# v1.net
KiCad netlist of a schematic drawn in EAGLE
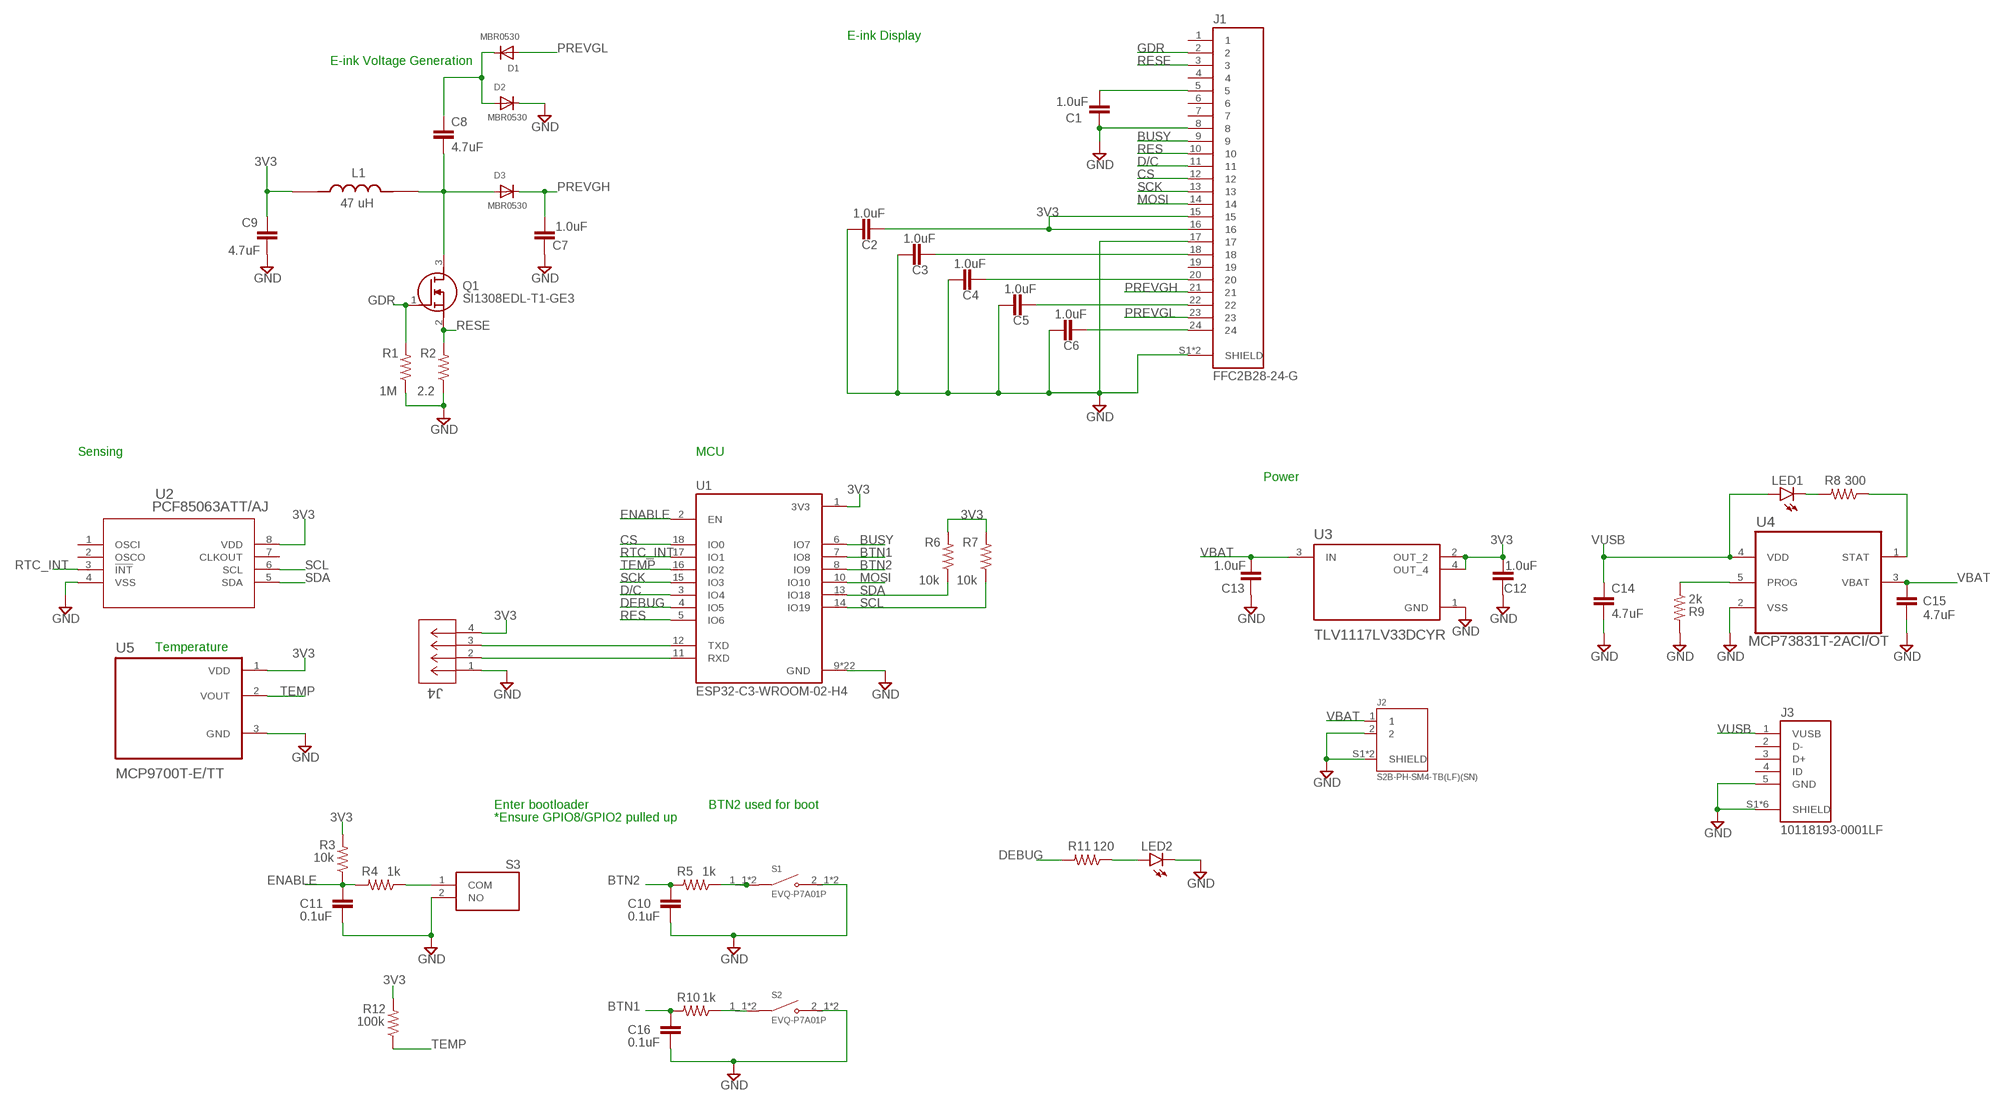
[diagram p0: schematic, sheet 1]

(export (version "E")
  (design (tool "Eeschema 10.0.6"))
  (components
    (comp (ref "C1")
      (value "1.0uF")
      (footprint "eagle-import:0603")
      (libsource (lib "eagle-import") (part "1.0UF-0603-16V-10%-X7R-WE"))
    )
    (comp (ref "C2")
      (value "1.0uF")
      (footprint "eagle-import:0603")
      (libsource (lib "eagle-import") (part "1.0UF-0603-16V-10%-X7R-WE"))
    )
    (comp (ref "C3")
      (value "1.0uF")
      (footprint "eagle-import:0603")
      (libsource (lib "eagle-import") (part "1.0UF-0603-16V-10%-X7R-WE"))
    )
    (comp (ref "C4")
      (value "1.0uF")
      (footprint "eagle-import:0603")
      (libsource (lib "eagle-import") (part "1.0UF-0603-16V-10%-X7R-WE"))
    )
    (comp (ref "C5")
      (value "1.0uF")
      (footprint "eagle-import:0603")
      (libsource (lib "eagle-import") (part "1.0UF-0603-16V-10%-X7R-WE"))
    )
    (comp (ref "C6")
      (value "1.0uF")
      (footprint "eagle-import:0603")
      (libsource (lib "eagle-import") (part "1.0UF-0603-16V-10%-X7R-WE"))
    )
    (comp (ref "C7")
      (value "1.0uF")
      (footprint "eagle-import:0603")
      (libsource (lib "eagle-import") (part "1.0UF-0603-16V-10%-X7R-WE"))
    )
    (comp (ref "C8")
      (value "4.7uF")
      (footprint "eagle-import:0603")
      (libsource (lib "eagle-import") (part "4.7UF-0603-35V-(20%)"))
    )
    (comp (ref "C9")
      (value "4.7uF")
      (footprint "eagle-import:0603")
      (libsource (lib "eagle-import") (part "4.7UF-0603-35V-(20%)"))
    )
    (comp (ref "C10")
      (value "0.1uF")
      (footprint "eagle-import:0603")
      (libsource (lib "eagle-import") (part "0.1UF-0603-25V-(+80/-20%)"))
    )
    (comp (ref "C11")
      (value "0.1uF")
      (footprint "eagle-import:0603")
      (libsource (lib "eagle-import") (part "0.1UF-0603-25V-(+80/-20%)"))
    )
    (comp (ref "C12")
      (value "1.0uF")
      (footprint "eagle-import:0603")
      (libsource (lib "eagle-import") (part "1.0UF-0603-16V-10%-X7R-WE"))
    )
    (comp (ref "C13")
      (value "1.0uF")
      (footprint "eagle-import:0603")
      (libsource (lib "eagle-import") (part "1.0UF-0603-16V-10%-X7R-WE"))
    )
    (comp (ref "C14")
      (value "4.7uF")
      (footprint "eagle-import:0603")
      (libsource (lib "eagle-import") (part "4.7UF-0603-35V-(20%)"))
    )
    (comp (ref "C15")
      (value "4.7uF")
      (footprint "eagle-import:0603")
      (libsource (lib "eagle-import") (part "4.7UF-0603-35V-(20%)"))
    )
    (comp (ref "C16")
      (value "0.1uF")
      (footprint "eagle-import:0603")
      (libsource (lib "eagle-import") (part "0.1UF-0603-25V-(+80/-20%)"))
    )
    (comp (ref "D1")
      (value "MBR0530")
      (footprint "eagle-import:SOD323F")
      (fields (field (name "MF") "ON Semiconductor"))
      (libsource (lib "eagle-import") (part "MBR0530"))
    )
    (comp (ref "D2")
      (value "MBR0530")
      (footprint "eagle-import:SOD323F")
      (fields (field (name "MF") "ON Semiconductor"))
      (libsource (lib "eagle-import") (part "MBR0530"))
    )
    (comp (ref "D3")
      (value "MBR0530")
      (footprint "eagle-import:SOD323F")
      (fields (field (name "MF") "ON Semiconductor"))
      (libsource (lib "eagle-import") (part "MBR0530"))
    )
    (comp (ref "J1")
      (value "FFC2B28-24-G")
      (footprint "eagle-import:GCT_FFC2B28-24-G")
      (fields (field (name "MF") "Global Connector Technology"))
      (libsource (lib "eagle-import") (part "FFC2B28-24-G"))
    )
    (comp (ref "J2")
      (value "S2B-PH-SM4-TB(LF)(SN)")
      (footprint "eagle-import:JST_S2B-PH-SM4-TB(LF)(SN)")
      (fields (field (name "MF") "JST Sales"))
      (libsource (lib "eagle-import") (part "S2B-PH-SM4-TB(LF)(SN)"))
    )
    (comp (ref "J3")
      (value "10118193-0001LF")
      (footprint "eagle-import:AMPHENOL_10118193-0001LF")
      (fields (field (name "MF") "Amphenol ICC"))
      (libsource (lib "eagle-import") (part "10118193-0001LF"))
    )
    (comp (ref "J4")
      (value "851-43-004-20-001000")
      (footprint "eagle-import:CONN_851-43-004-20-001000_MIM")
      (fields (field (name "COPYRIGHT") "Copyright (C) 2024 Ultra Librarian. All rights reserved."))
      (libsource (lib "eagle-import") (part "851-43-004-20-001000"))
    )
    (comp (ref "L1")
      (value "47 uH")
      (footprint "eagle-import:IND_ADL3225V-470MT-TL000")
      (fields (field (name "MF") "TDK") (field (name "MP") "ADL3225V-470MT-TL000"))
      (libsource (lib "eagle-import") (part "ADL3225V-470MT-TL000"))
    )
    (comp (ref "LED1")
      (value "LEDCHIP-LED0603")
      (footprint "eagle-import:CHIP-LED0603")
      (libsource (lib "eagle-import") (part "LEDCHIP-LED0603"))
    )
    (comp (ref "LED2")
      (value "LEDCHIP-LED0603")
      (footprint "eagle-import:CHIP-LED0603")
      (libsource (lib "eagle-import") (part "LEDCHIP-LED0603"))
    )
    (comp (ref "Q1")
      (value "SI1308EDL-T1-GE3")
      (footprint "eagle-import:SOT65P210X110-3N")
      (fields (field (name "MF") "Vishay Siliconix"))
      (libsource (lib "eagle-import") (part "SI1308EDL-T1-GE3"))
    )
    (comp (ref "R1")
      (value "1M")
      (footprint "eagle-import:R0603")
      (libsource (lib "eagle-import") (part "R-US_R0603"))
    )
    (comp (ref "R2")
      (value "2.2")
      (footprint "eagle-import:R0603")
      (libsource (lib "eagle-import") (part "R-US_R0603"))
    )
    (comp (ref "R3")
      (value "10k")
      (footprint "eagle-import:R0603")
      (libsource (lib "eagle-import") (part "R-US_R0603"))
    )
    (comp (ref "R4")
      (value "1k")
      (footprint "eagle-import:R0603")
      (libsource (lib "eagle-import") (part "R-US_R0603"))
    )
    (comp (ref "R5")
      (value "1k")
      (footprint "eagle-import:R0603")
      (libsource (lib "eagle-import") (part "R-US_R0603"))
    )
    (comp (ref "R6")
      (value "10k")
      (footprint "eagle-import:R0603")
      (libsource (lib "eagle-import") (part "R-US_R0603"))
    )
    (comp (ref "R7")
      (value "10k")
      (footprint "eagle-import:R0603")
      (libsource (lib "eagle-import") (part "R-US_R0603"))
    )
    (comp (ref "R8")
      (value "300")
      (footprint "eagle-import:R0603")
      (libsource (lib "eagle-import") (part "R-US_R0603"))
    )
    (comp (ref "R9")
      (value "2k")
      (footprint "eagle-import:R0603")
      (libsource (lib "eagle-import") (part "R-US_R0603"))
    )
    (comp (ref "R10")
      (value "1k")
      (footprint "eagle-import:R0603")
      (libsource (lib "eagle-import") (part "R-US_R0603"))
    )
    (comp (ref "R11")
      (value "120")
      (footprint "eagle-import:R0603")
      (libsource (lib "eagle-import") (part "R-US_R0603"))
    )
    (comp (ref "R12")
      (value "100k")
      (footprint "eagle-import:R0603")
      (libsource (lib "eagle-import") (part "R-US_R0603"))
    )
    (comp (ref "S1")
      (value "EVQ-P7A01P")
      (footprint "eagle-import:SW_EVQ-P7A01P")
      (fields (field (name "MF") "Panasonic Electronic Components"))
      (libsource (lib "eagle-import") (part "EVQ-P7A01P"))
    )
    (comp (ref "S2")
      (value "EVQ-P7A01P")
      (footprint "eagle-import:SW_EVQ-P7A01P")
      (fields (field (name "MF") "Panasonic Electronic Components"))
      (libsource (lib "eagle-import") (part "EVQ-P7A01P"))
    )
    (comp (ref "S3")
      (value "PTS636_SM25F_SMTR_LFS")
      (footprint "eagle-import:PTS636SM25FSMTRLFS")
      (fields (field (name "MF") "C&K") (field (name "MP") "PTS636 SM25F SMTR LFS"))
      (libsource (lib "eagle-import") (part "PTS636_SM25F_SMTR_LFS"))
    )
    (comp (ref "U1")
      (value "ESP32-C3-WROOM-02-H4")
      (footprint "eagle-import:MODULE_ESP32-C3-WROOM-02-H4")
      (fields (field (name "MF") "Espressif Systems"))
      (libsource (lib "eagle-import") (part "ESP32-C3-WROOM-02-H4"))
    )
    (comp (ref "U2")
      (value "PCF85063ATT/AJ")
      (footprint "eagle-import:PCF85063ATT_AJ_NXP")
      (fields (field (name "COPYRIGHT") "Copyright (C) 2024 Ultra Librarian. All rights reserved."))
      (libsource (lib "eagle-import") (part "PCF85063ATT/AJ"))
    )
    (comp (ref "U3")
      (value "TLV1117LV33DCYR")
      (footprint "eagle-import:VREG_TLV1117LV33DCYR")
      (fields (field (name "MF") "Texas Instruments"))
      (libsource (lib "eagle-import") (part "TLV1117LV33DCYR"))
    )
    (comp (ref "U4")
      (value "MCP73831T-2ACI/OT")
      (footprint "eagle-import:SOT95P280X145-5N")
      (fields (field (name "MF") "Microchip"))
      (libsource (lib "eagle-import") (part "MCP73831T-2ACI/OT"))
    )
    (comp (ref "U5")
      (value "MCP9700T-E/TT")
      (footprint "eagle-import:SOT95P237X112-3N")
      (fields (field (name "MF") "Microchip"))
      (libsource (lib "eagle-import") (part "MCP9700T-E/TT"))
    )
  )
  (nets
    (net (code "1") (name "/3V3") (class "Default")
      (node (ref "C12") (pin "1") (pinfunction "1_1") (pintype "passive"))
      (node (ref "C2") (pin "1") (pinfunction "1_1") (pintype "passive"))
      (node (ref "C9") (pin "1") (pinfunction "1_1") (pintype "passive"))
      (node (ref "J1") (pin "15") (pinfunction "15_15") (pintype "passive"))
      (node (ref "J1") (pin "16") (pinfunction "16_16") (pintype "passive"))
      (node (ref "J4") (pin "4") (pinfunction "4_4") (pintype "passive"))
      (node (ref "L1") (pin "1") (pinfunction "1_1") (pintype "passive"))
      (node (ref "R12") (pin "2") (pinfunction "2_2") (pintype "passive"))
      (node (ref "R3") (pin "2") (pinfunction "2_2") (pintype "passive"))
      (node (ref "R6") (pin "2") (pinfunction "2_2") (pintype "passive"))
      (node (ref "R7") (pin "2") (pinfunction "2_2") (pintype "passive"))
      (node (ref "U1") (pin "1") (pinfunction "3V3_1") (pintype "power_in"))
      (node (ref "U2") (pin "8") (pinfunction "VDD_8") (pintype "power_in"))
      (node (ref "U3") (pin "2") (pinfunction "OUT_2_2") (pintype "output"))
      (node (ref "U3") (pin "4") (pinfunction "OUT_4_4") (pintype "output"))
      (node (ref "U5") (pin "1") (pinfunction "VDD_1") (pintype "power_in"))
    )
    (net (code "2") (name "/BTN1") (class "Default")
      (node (ref "C16") (pin "1") (pinfunction "1_1") (pintype "passive"))
      (node (ref "R10") (pin "2") (pinfunction "2_2") (pintype "passive"))
      (node (ref "U1") (pin "7") (pinfunction "IO8_7") (pintype "bidirectional"))
    )
    (net (code "3") (name "/BTN2") (class "Default")
      (node (ref "C10") (pin "1") (pinfunction "1_1") (pintype "passive"))
      (node (ref "R5") (pin "2") (pinfunction "2_2") (pintype "passive"))
      (node (ref "U1") (pin "8") (pinfunction "IO9_8") (pintype "bidirectional"))
    )
    (net (code "4") (name "/BUSY") (class "Default")
      (node (ref "J1") (pin "9") (pinfunction "9_9") (pintype "passive"))
      (node (ref "U1") (pin "6") (pinfunction "IO7_6") (pintype "bidirectional"))
    )
    (net (code "5") (name "/CS") (class "Default")
      (node (ref "J1") (pin "12") (pinfunction "12_12") (pintype "passive"))
      (node (ref "U1") (pin "18") (pinfunction "IO0_18") (pintype "bidirectional"))
    )
    (net (code "6") (name "/DEBUG") (class "Default")
      (node (ref "R11") (pin "2") (pinfunction "2_2") (pintype "passive"))
      (node (ref "U1") (pin "4") (pinfunction "IO5_4") (pintype "bidirectional"))
    )
    (net (code "7") (name "/D{slash}C") (class "Default")
      (node (ref "J1") (pin "11") (pinfunction "11_11") (pintype "passive"))
      (node (ref "U1") (pin "3") (pinfunction "IO4_3") (pintype "bidirectional"))
    )
    (net (code "8") (name "/ENABLE") (class "Default")
      (node (ref "C11") (pin "1") (pinfunction "1_1") (pintype "passive"))
      (node (ref "R3") (pin "1") (pinfunction "1_1") (pintype "passive"))
      (node (ref "R4") (pin "2") (pinfunction "2_2") (pintype "passive"))
      (node (ref "U1") (pin "2") (pinfunction "EN_2") (pintype "input"))
    )
    (net (code "9") (name "/GDR") (class "Default")
      (node (ref "J1") (pin "2") (pinfunction "2_2") (pintype "passive"))
      (node (ref "Q1") (pin "1") (pinfunction "G_1") (pintype "bidirectional"))
      (node (ref "R1") (pin "2") (pinfunction "2_2") (pintype "passive"))
    )
    (net (code "10") (name "/MOSI") (class "Default")
      (node (ref "J1") (pin "14") (pinfunction "14_14") (pintype "passive"))
      (node (ref "U1") (pin "10") (pinfunction "IO10_10") (pintype "bidirectional"))
    )
    (net (code "11") (name "/PREVGH") (class "Default")
      (node (ref "C7") (pin "1") (pinfunction "1_1") (pintype "passive"))
      (node (ref "D3") (pin "C") (pinfunction "C_C") (pintype "passive"))
      (node (ref "J1") (pin "21") (pinfunction "21_21") (pintype "passive"))
    )
    (net (code "12") (name "/PREVGL") (class "Default")
      (node (ref "D1") (pin "A") (pinfunction "A_A") (pintype "passive"))
      (node (ref "J1") (pin "23") (pinfunction "23_23") (pintype "passive"))
    )
    (net (code "13") (name "/RES") (class "Default")
      (node (ref "J1") (pin "10") (pinfunction "10_10") (pintype "passive"))
      (node (ref "U1") (pin "5") (pinfunction "IO6_5") (pintype "bidirectional"))
    )
    (net (code "14") (name "/RESE") (class "Default")
      (node (ref "J1") (pin "3") (pinfunction "3_3") (pintype "passive"))
      (node (ref "Q1") (pin "2") (pinfunction "S_2") (pintype "bidirectional"))
      (node (ref "R2") (pin "2") (pinfunction "2_2") (pintype "passive"))
    )
    (net (code "15") (name "/RTC_INT") (class "Default")
      (node (ref "U1") (pin "17") (pinfunction "IO1_17") (pintype "bidirectional"))
      (node (ref "U2") (pin "3") (pinfunction "~{INT}_3") (pintype "output"))
    )
    (net (code "16") (name "/SCK") (class "Default")
      (node (ref "J1") (pin "13") (pinfunction "13_13") (pintype "passive"))
      (node (ref "U1") (pin "15") (pinfunction "IO3_15") (pintype "bidirectional"))
    )
    (net (code "17") (name "/SCL") (class "Default")
      (node (ref "R7") (pin "1") (pinfunction "1_1") (pintype "passive"))
      (node (ref "U1") (pin "14") (pinfunction "IO19_14") (pintype "bidirectional"))
      (node (ref "U2") (pin "6") (pinfunction "SCL_6") (pintype "input"))
    )
    (net (code "18") (name "/SDA") (class "Default")
      (node (ref "R6") (pin "1") (pinfunction "1_1") (pintype "passive"))
      (node (ref "U1") (pin "13") (pinfunction "IO18_13") (pintype "bidirectional"))
      (node (ref "U2") (pin "5") (pinfunction "SDA_5") (pintype "bidirectional"))
    )
    (net (code "19") (name "/TEMP") (class "Default")
      (node (ref "R12") (pin "1") (pinfunction "1_1") (pintype "passive"))
      (node (ref "U1") (pin "16") (pinfunction "IO2_16") (pintype "bidirectional"))
      (node (ref "U5") (pin "2") (pinfunction "VOUT_2") (pintype "output"))
    )
    (net (code "20") (name "/VBAT") (class "Default")
      (node (ref "C13") (pin "1") (pinfunction "1_1") (pintype "passive"))
      (node (ref "C15") (pin "1") (pinfunction "1_1") (pintype "passive"))
      (node (ref "J2") (pin "1") (pinfunction "1_1") (pintype "passive"))
      (node (ref "U3") (pin "3") (pinfunction "IN_3") (pintype "input"))
      (node (ref "U4") (pin "3") (pinfunction "VBAT_3") (pintype "output"))
    )
    (net (code "21") (name "/VUSB") (class "Default")
      (node (ref "C14") (pin "1") (pinfunction "1_1") (pintype "passive"))
      (node (ref "J3") (pin "1") (pinfunction "VUSB_1") (pintype "passive"))
      (node (ref "LED1") (pin "A") (pinfunction "A_A") (pintype "passive"))
      (node (ref "U4") (pin "4") (pinfunction "VDD_4") (pintype "power_in"))
    )
    (net (code "22") (name "GND") (class "Default")
      (node (ref "C1") (pin "2") (pinfunction "2_2") (pintype "passive"))
      (node (ref "C10") (pin "2") (pinfunction "2_2") (pintype "passive"))
      (node (ref "C11") (pin "2") (pinfunction "2_2") (pintype "passive"))
      (node (ref "C12") (pin "2") (pinfunction "2_2") (pintype "passive"))
      (node (ref "C13") (pin "2") (pinfunction "2_2") (pintype "passive"))
      (node (ref "C14") (pin "2") (pinfunction "2_2") (pintype "passive"))
      (node (ref "C15") (pin "2") (pinfunction "2_2") (pintype "passive"))
      (node (ref "C16") (pin "2") (pinfunction "2_2") (pintype "passive"))
      (node (ref "C2") (pin "2") (pinfunction "2_2") (pintype "passive"))
      (node (ref "C3") (pin "2") (pinfunction "2_2") (pintype "passive"))
      (node (ref "C4") (pin "2") (pinfunction "2_2") (pintype "passive"))
      (node (ref "C5") (pin "2") (pinfunction "2_2") (pintype "passive"))
      (node (ref "C6") (pin "2") (pinfunction "2_2") (pintype "passive"))
      (node (ref "C7") (pin "2") (pinfunction "2_2") (pintype "passive"))
      (node (ref "C9") (pin "2") (pinfunction "2_2") (pintype "passive"))
      (node (ref "D2") (pin "C") (pinfunction "C_C") (pintype "passive"))
      (node (ref "J1") (pin "17") (pinfunction "17_17") (pintype "passive"))
      (node (ref "J1") (pin "8") (pinfunction "8_8") (pintype "passive"))
      (node (ref "J1") (pin "S1") (pinfunction "SHIELD_S1") (pintype "passive"))
      (node (ref "J1") (pin "S2") (pinfunction "SHIELD_S2") (pintype "passive"))
      (node (ref "J2") (pin "2") (pinfunction "2_2") (pintype "passive"))
      (node (ref "J2") (pin "S1") (pinfunction "SHIELD_S1") (pintype "passive"))
      (node (ref "J2") (pin "S2") (pinfunction "SHIELD_S2") (pintype "passive"))
      (node (ref "J3") (pin "5") (pinfunction "GND_5") (pintype "passive"))
      (node (ref "J3") (pin "S1") (pinfunction "SHIELD_S1") (pintype "passive"))
      (node (ref "J3") (pin "S2") (pinfunction "SHIELD_S2") (pintype "passive"))
      (node (ref "J3") (pin "S3") (pinfunction "SHIELD_S3") (pintype "passive"))
      (node (ref "J3") (pin "S4") (pinfunction "SHIELD_S4") (pintype "passive"))
      (node (ref "J3") (pin "S5") (pinfunction "SHIELD_S5") (pintype "passive"))
      (node (ref "J3") (pin "S6") (pinfunction "SHIELD_S6") (pintype "passive"))
      (node (ref "J4") (pin "1") (pinfunction "1_1") (pintype "passive"))
      (node (ref "LED2") (pin "C") (pinfunction "C_C") (pintype "passive"))
      (node (ref "R1") (pin "1") (pinfunction "1_1") (pintype "passive"))
      (node (ref "R2") (pin "1") (pinfunction "1_1") (pintype "passive"))
      (node (ref "R9") (pin "2") (pinfunction "2_2") (pintype "passive"))
      (node (ref "S1") (pin "2_1") (pinfunction "2_2_1") (pintype "passive"))
      (node (ref "S1") (pin "2_2") (pinfunction "2_2_2") (pintype "passive"))
      (node (ref "S2") (pin "2_1") (pinfunction "2_2_1") (pintype "passive"))
      (node (ref "S2") (pin "2_2") (pinfunction "2_2_2") (pintype "passive"))
      (node (ref "S3") (pin "2") (pinfunction "NO_2") (pintype "bidirectional"))
      (node (ref "U1") (pin "19") (pinfunction "GND_19") (pintype "power_in"))
      (node (ref "U1") (pin "20") (pinfunction "GND_20") (pintype "power_in"))
      (node (ref "U1") (pin "21") (pinfunction "GND_21") (pintype "power_in"))
      (node (ref "U1") (pin "22") (pinfunction "GND_22") (pintype "power_in"))
      (node (ref "U1") (pin "23") (pinfunction "GND_23") (pintype "power_in"))
      (node (ref "U1") (pin "24") (pinfunction "GND_24") (pintype "power_in"))
      (node (ref "U1") (pin "25") (pinfunction "GND_25") (pintype "power_in"))
      (node (ref "U1") (pin "26") (pinfunction "GND_26") (pintype "power_in"))
      (node (ref "U1") (pin "27") (pinfunction "GND_27") (pintype "power_in"))
      (node (ref "U1") (pin "28") (pinfunction "GND_28") (pintype "power_in"))
      (node (ref "U1") (pin "29") (pinfunction "GND_29") (pintype "power_in"))
      (node (ref "U1") (pin "30") (pinfunction "GND_30") (pintype "power_in"))
      (node (ref "U1") (pin "31") (pinfunction "GND_31") (pintype "power_in"))
      (node (ref "U1") (pin "32") (pinfunction "GND_32") (pintype "power_in"))
      (node (ref "U1") (pin "33") (pinfunction "GND_33") (pintype "power_in"))
      (node (ref "U1") (pin "34") (pinfunction "GND_34") (pintype "power_in"))
      (node (ref "U1") (pin "35") (pinfunction "GND_35") (pintype "power_in"))
      (node (ref "U1") (pin "36") (pinfunction "GND_36") (pintype "power_in"))
      (node (ref "U1") (pin "37") (pinfunction "GND_37") (pintype "power_in"))
      (node (ref "U1") (pin "38") (pinfunction "GND_38") (pintype "power_in"))
      (node (ref "U1") (pin "39") (pinfunction "GND_39") (pintype "power_in"))
      (node (ref "U1") (pin "9") (pinfunction "GND_9") (pintype "power_in"))
      (node (ref "U2") (pin "4") (pinfunction "VSS_4") (pintype "passive"))
      (node (ref "U3") (pin "1") (pinfunction "GND_1") (pintype "power_in"))
      (node (ref "U4") (pin "2") (pinfunction "VSS_2") (pintype "power_in"))
      (node (ref "U5") (pin "3") (pinfunction "GND_3") (pintype "power_in"))
    )
    (net (code "23") (name "Net-(C1-Pad1)") (class "Default")
      (node (ref "C1") (pin "1") (pinfunction "1_1") (pintype "passive"))
      (node (ref "J1") (pin "5") (pinfunction "5_5") (pintype "passive"))
    )
    (net (code "24") (name "Net-(C3-Pad1)") (class "Default")
      (node (ref "C3") (pin "1") (pinfunction "1_1") (pintype "passive"))
      (node (ref "J1") (pin "18") (pinfunction "18_18") (pintype "passive"))
    )
    (net (code "25") (name "Net-(C4-Pad1)") (class "Default")
      (node (ref "C4") (pin "1") (pinfunction "1_1") (pintype "passive"))
      (node (ref "J1") (pin "20") (pinfunction "20_20") (pintype "passive"))
    )
    (net (code "26") (name "Net-(C5-Pad1)") (class "Default")
      (node (ref "C5") (pin "1") (pinfunction "1_1") (pintype "passive"))
      (node (ref "J1") (pin "22") (pinfunction "22_22") (pintype "passive"))
    )
    (net (code "27") (name "Net-(C6-Pad1)") (class "Default")
      (node (ref "C6") (pin "1") (pinfunction "1_1") (pintype "passive"))
      (node (ref "J1") (pin "24") (pinfunction "24_24") (pintype "passive"))
    )
    (net (code "28") (name "Net-(C8-Pad1)") (class "Default")
      (node (ref "C8") (pin "1") (pinfunction "1_1") (pintype "passive"))
      (node (ref "D1") (pin "C") (pinfunction "C_C") (pintype "passive"))
      (node (ref "D2") (pin "A") (pinfunction "A_A") (pintype "passive"))
    )
    (net (code "29") (name "Net-(LED1-PadC)") (class "Default")
      (node (ref "LED1") (pin "C") (pinfunction "C_C") (pintype "passive"))
      (node (ref "R8") (pin "2") (pinfunction "2_2") (pintype "passive"))
    )
    (net (code "30") (name "Net-(LED2-PadA)") (class "Default")
      (node (ref "LED2") (pin "A") (pinfunction "A_A") (pintype "passive"))
      (node (ref "R11") (pin "1") (pinfunction "1_1") (pintype "passive"))
    )
    (net (code "31") (name "Net-(Q1-D)") (class "Default")
      (node (ref "C8") (pin "2") (pinfunction "2_2") (pintype "passive"))
      (node (ref "D3") (pin "A") (pinfunction "A_A") (pintype "passive"))
      (node (ref "L1") (pin "2") (pinfunction "2_2") (pintype "passive"))
      (node (ref "Q1") (pin "3") (pinfunction "D_3") (pintype "bidirectional"))
    )
    (net (code "32") (name "Net-(R5-Pad1)") (class "Default")
      (node (ref "R5") (pin "1") (pinfunction "1_1") (pintype "passive"))
      (node (ref "S1") (pin "1_1") (pinfunction "1_1_1") (pintype "passive"))
      (node (ref "S1") (pin "1_2") (pinfunction "1_1_2") (pintype "passive"))
    )
    (net (code "33") (name "Net-(R10-Pad1)") (class "Default")
      (node (ref "R10") (pin "1") (pinfunction "1_1") (pintype "passive"))
      (node (ref "S2") (pin "1_1") (pinfunction "1_1_1") (pintype "passive"))
      (node (ref "S2") (pin "1_2") (pinfunction "1_1_2") (pintype "passive"))
    )
    (net (code "34") (name "Net-(S3-COM)") (class "Default")
      (node (ref "R4") (pin "1") (pinfunction "1_1") (pintype "passive"))
      (node (ref "S3") (pin "1") (pinfunction "COM_1") (pintype "bidirectional"))
    )
    (net (code "35") (name "Net-(U1-RXD)") (class "Default")
      (node (ref "J4") (pin "2") (pinfunction "2_2") (pintype "passive"))
      (node (ref "U1") (pin "11") (pinfunction "RXD_11") (pintype "bidirectional"))
    )
    (net (code "36") (name "Net-(U1-TXD)") (class "Default")
      (node (ref "J4") (pin "3") (pinfunction "3_3") (pintype "passive"))
      (node (ref "U1") (pin "12") (pinfunction "TXD_12") (pintype "bidirectional"))
    )
    (net (code "37") (name "Net-(U4-PROG)") (class "Default")
      (node (ref "R9") (pin "1") (pinfunction "1_1") (pintype "passive"))
      (node (ref "U4") (pin "5") (pinfunction "PROG_5") (pintype "input"))
    )
    (net (code "38") (name "Net-(U4-STAT)") (class "Default")
      (node (ref "R8") (pin "1") (pinfunction "1_1") (pintype "passive"))
      (node (ref "U4") (pin "1") (pinfunction "STAT_1") (pintype "output"))
    )
    (net (code "39") (name "unconnected-(J1-Pad1)") (class "Default")
      (node (ref "J1") (pin "1") (pinfunction "1_1") (pintype "passive"))
    )
    (net (code "40") (name "unconnected-(J1-Pad4)") (class "Default")
      (node (ref "J1") (pin "4") (pinfunction "4_4") (pintype "passive"))
    )
    (net (code "41") (name "unconnected-(J1-Pad6)") (class "Default")
      (node (ref "J1") (pin "6") (pinfunction "6_6") (pintype "passive"))
    )
    (net (code "42") (name "unconnected-(J1-Pad7)") (class "Default")
      (node (ref "J1") (pin "7") (pinfunction "7_7") (pintype "passive"))
    )
    (net (code "43") (name "unconnected-(J1-Pad19)") (class "Default")
      (node (ref "J1") (pin "19") (pinfunction "19_19") (pintype "passive"))
    )
    (net (code "44") (name "unconnected-(J3-D+-Pad3)") (class "Default")
      (node (ref "J3") (pin "3") (pinfunction "D+_3") (pintype "passive"))
    )
    (net (code "45") (name "unconnected-(J3-D--Pad2)") (class "Default")
      (node (ref "J3") (pin "2") (pinfunction "D-_2") (pintype "passive"))
    )
    (net (code "46") (name "unconnected-(J3-ID-Pad4)") (class "Default")
      (node (ref "J3") (pin "4") (pinfunction "ID_4") (pintype "passive"))
    )
    (net (code "47") (name "unconnected-(U2-CLKOUT-Pad7)") (class "Default")
      (node (ref "U2") (pin "7") (pinfunction "CLKOUT_7") (pintype "output"))
    )
    (net (code "48") (name "unconnected-(U2-OSCI-Pad1)") (class "Default")
      (node (ref "U2") (pin "1") (pinfunction "OSCI_1") (pintype "input"))
    )
    (net (code "49") (name "unconnected-(U2-OSCO-Pad2)") (class "Default")
      (node (ref "U2") (pin "2") (pinfunction "OSCO_2") (pintype "output"))
    )
  )
)
